# M906X.net
KiCad netlist of a schematic drawn in EAGLE
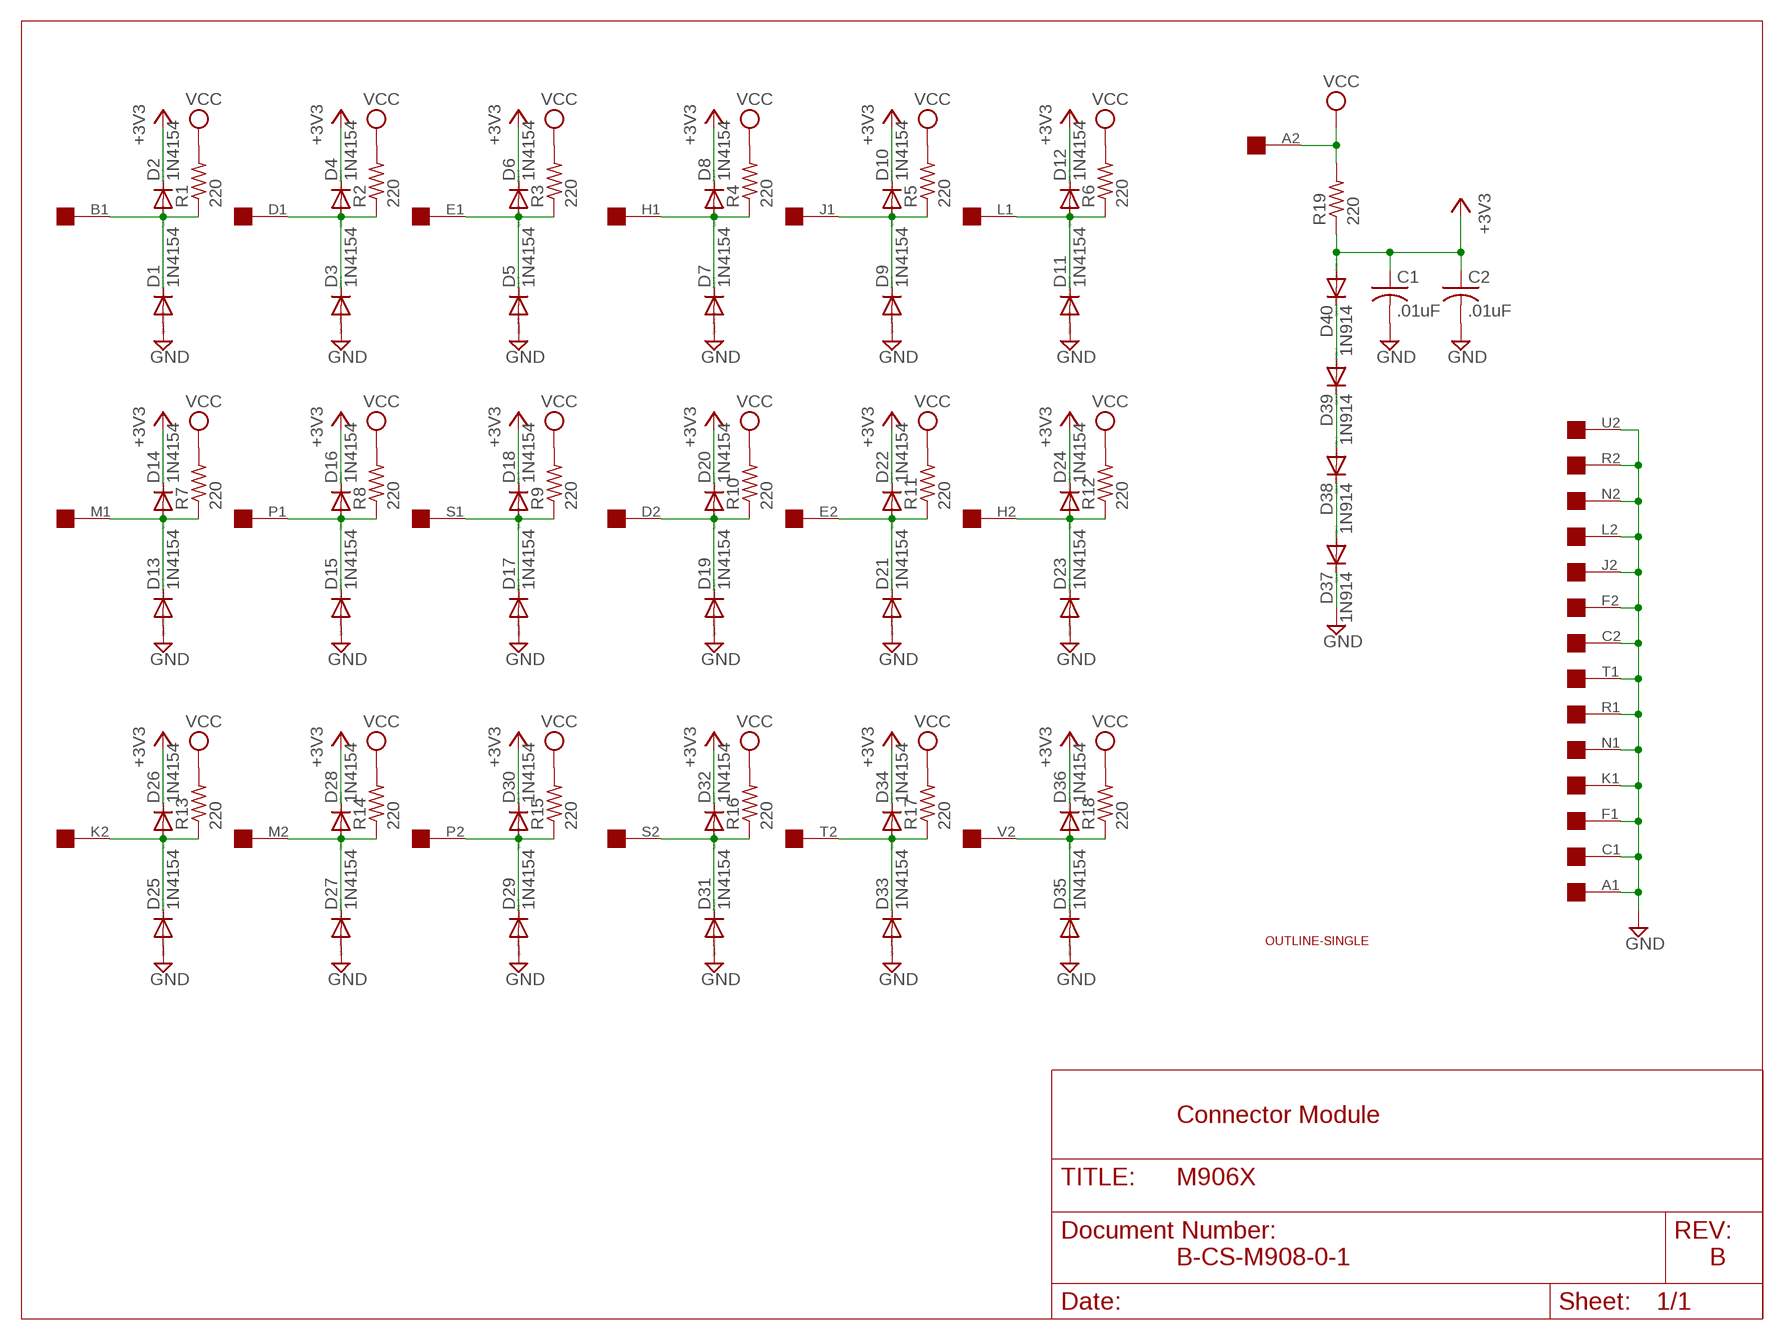
[diagram p0: schematic, sheet 1]

(export (version "E")
  (design (tool "Eeschema 10.0.6"))
  (components
    (comp (ref "C1")
      (value ".01uF")
      (footprint "eagle-import:C050-025X075")
      (libsource (lib "eagle-import") (part "C-US050-025X075"))
    )
    (comp (ref "C2")
      (value ".01uF")
      (footprint "eagle-import:C050-025X075")
      (libsource (lib "eagle-import") (part "C-US050-025X075"))
    )
    (comp (ref "D1")
      (value "1N4154")
      (footprint "eagle-import:DO35-10")
      (libsource (lib "eagle-import") (part "1N4148DO35-10"))
    )
    (comp (ref "D2")
      (value "1N4154")
      (footprint "eagle-import:DO35-10")
      (libsource (lib "eagle-import") (part "1N4148DO35-10"))
    )
    (comp (ref "D3")
      (value "1N4154")
      (footprint "eagle-import:DO35-10")
      (libsource (lib "eagle-import") (part "1N4148DO35-10"))
    )
    (comp (ref "D4")
      (value "1N4154")
      (footprint "eagle-import:DO35-10")
      (libsource (lib "eagle-import") (part "1N4148DO35-10"))
    )
    (comp (ref "D5")
      (value "1N4154")
      (footprint "eagle-import:DO35-10")
      (libsource (lib "eagle-import") (part "1N4148DO35-10"))
    )
    (comp (ref "D6")
      (value "1N4154")
      (footprint "eagle-import:DO35-10")
      (libsource (lib "eagle-import") (part "1N4148DO35-10"))
    )
    (comp (ref "D7")
      (value "1N4154")
      (footprint "eagle-import:DO35-10")
      (libsource (lib "eagle-import") (part "1N4148DO35-10"))
    )
    (comp (ref "D8")
      (value "1N4154")
      (footprint "eagle-import:DO35-10")
      (libsource (lib "eagle-import") (part "1N4148DO35-10"))
    )
    (comp (ref "D9")
      (value "1N4154")
      (footprint "eagle-import:DO35-10")
      (libsource (lib "eagle-import") (part "1N4148DO35-10"))
    )
    (comp (ref "D10")
      (value "1N4154")
      (footprint "eagle-import:DO35-10")
      (libsource (lib "eagle-import") (part "1N4148DO35-10"))
    )
    (comp (ref "D11")
      (value "1N4154")
      (footprint "eagle-import:DO35-10")
      (libsource (lib "eagle-import") (part "1N4148DO35-10"))
    )
    (comp (ref "D12")
      (value "1N4154")
      (footprint "eagle-import:DO35-10")
      (libsource (lib "eagle-import") (part "1N4148DO35-10"))
    )
    (comp (ref "D13")
      (value "1N4154")
      (footprint "eagle-import:DO35-10")
      (libsource (lib "eagle-import") (part "1N4148DO35-10"))
    )
    (comp (ref "D14")
      (value "1N4154")
      (footprint "eagle-import:DO35-10")
      (libsource (lib "eagle-import") (part "1N4148DO35-10"))
    )
    (comp (ref "D15")
      (value "1N4154")
      (footprint "eagle-import:DO35-10")
      (libsource (lib "eagle-import") (part "1N4148DO35-10"))
    )
    (comp (ref "D16")
      (value "1N4154")
      (footprint "eagle-import:DO35-10")
      (libsource (lib "eagle-import") (part "1N4148DO35-10"))
    )
    (comp (ref "D17")
      (value "1N4154")
      (footprint "eagle-import:DO35-10")
      (libsource (lib "eagle-import") (part "1N4148DO35-10"))
    )
    (comp (ref "D18")
      (value "1N4154")
      (footprint "eagle-import:DO35-10")
      (libsource (lib "eagle-import") (part "1N4148DO35-10"))
    )
    (comp (ref "D19")
      (value "1N4154")
      (footprint "eagle-import:DO35-10")
      (libsource (lib "eagle-import") (part "1N4148DO35-10"))
    )
    (comp (ref "D20")
      (value "1N4154")
      (footprint "eagle-import:DO35-10")
      (libsource (lib "eagle-import") (part "1N4148DO35-10"))
    )
    (comp (ref "D21")
      (value "1N4154")
      (footprint "eagle-import:DO35-10")
      (libsource (lib "eagle-import") (part "1N4148DO35-10"))
    )
    (comp (ref "D22")
      (value "1N4154")
      (footprint "eagle-import:DO35-10")
      (libsource (lib "eagle-import") (part "1N4148DO35-10"))
    )
    (comp (ref "D23")
      (value "1N4154")
      (footprint "eagle-import:DO35-10")
      (libsource (lib "eagle-import") (part "1N4148DO35-10"))
    )
    (comp (ref "D24")
      (value "1N4154")
      (footprint "eagle-import:DO35-10")
      (libsource (lib "eagle-import") (part "1N4148DO35-10"))
    )
    (comp (ref "D25")
      (value "1N4154")
      (footprint "eagle-import:DO35-10")
      (libsource (lib "eagle-import") (part "1N4148DO35-10"))
    )
    (comp (ref "D26")
      (value "1N4154")
      (footprint "eagle-import:DO35-10")
      (libsource (lib "eagle-import") (part "1N4148DO35-10"))
    )
    (comp (ref "D27")
      (value "1N4154")
      (footprint "eagle-import:DO35-10")
      (libsource (lib "eagle-import") (part "1N4148DO35-10"))
    )
    (comp (ref "D28")
      (value "1N4154")
      (footprint "eagle-import:DO35-10")
      (libsource (lib "eagle-import") (part "1N4148DO35-10"))
    )
    (comp (ref "D29")
      (value "1N4154")
      (footprint "eagle-import:DO35-10")
      (libsource (lib "eagle-import") (part "1N4148DO35-10"))
    )
    (comp (ref "D30")
      (value "1N4154")
      (footprint "eagle-import:DO35-10")
      (libsource (lib "eagle-import") (part "1N4148DO35-10"))
    )
    (comp (ref "D31")
      (value "1N4154")
      (footprint "eagle-import:DO35-10")
      (libsource (lib "eagle-import") (part "1N4148DO35-10"))
    )
    (comp (ref "D32")
      (value "1N4154")
      (footprint "eagle-import:DO35-10")
      (libsource (lib "eagle-import") (part "1N4148DO35-10"))
    )
    (comp (ref "D33")
      (value "1N4154")
      (footprint "eagle-import:DO35-10")
      (libsource (lib "eagle-import") (part "1N4148DO35-10"))
    )
    (comp (ref "D34")
      (value "1N4154")
      (footprint "eagle-import:DO35-10")
      (libsource (lib "eagle-import") (part "1N4148DO35-10"))
    )
    (comp (ref "D35")
      (value "1N4154")
      (footprint "eagle-import:DO35-10")
      (libsource (lib "eagle-import") (part "1N4148DO35-10"))
    )
    (comp (ref "D36")
      (value "1N4154")
      (footprint "eagle-import:DO35-10")
      (libsource (lib "eagle-import") (part "1N4148DO35-10"))
    )
    (comp (ref "D37")
      (value "1N914")
      (footprint "eagle-import:DO35-10")
      (libsource (lib "eagle-import") (part "1N4148DO35-10"))
    )
    (comp (ref "D38")
      (value "1N914")
      (footprint "eagle-import:DO35-10")
      (libsource (lib "eagle-import") (part "1N4148DO35-10"))
    )
    (comp (ref "D39")
      (value "1N914")
      (footprint "eagle-import:DO35-10")
      (libsource (lib "eagle-import") (part "1N4148DO35-10"))
    )
    (comp (ref "D40")
      (value "1N914")
      (footprint "eagle-import:DO35-10")
      (libsource (lib "eagle-import") (part "1N4148DO35-10"))
    )
    (comp (ref "R1")
      (value "220")
      (footprint "eagle-import:0207_10")
      (libsource (lib "eagle-import") (part "R-US_0207/10"))
    )
    (comp (ref "R2")
      (value "220")
      (footprint "eagle-import:0207_10")
      (libsource (lib "eagle-import") (part "R-US_0207/10"))
    )
    (comp (ref "R3")
      (value "220")
      (footprint "eagle-import:0207_10")
      (libsource (lib "eagle-import") (part "R-US_0207/10"))
    )
    (comp (ref "R4")
      (value "220")
      (footprint "eagle-import:0207_10")
      (libsource (lib "eagle-import") (part "R-US_0207/10"))
    )
    (comp (ref "R5")
      (value "220")
      (footprint "eagle-import:0207_10")
      (libsource (lib "eagle-import") (part "R-US_0207/10"))
    )
    (comp (ref "R6")
      (value "220")
      (footprint "eagle-import:0207_10")
      (libsource (lib "eagle-import") (part "R-US_0207/10"))
    )
    (comp (ref "R7")
      (value "220")
      (footprint "eagle-import:0207_10")
      (libsource (lib "eagle-import") (part "R-US_0207/10"))
    )
    (comp (ref "R8")
      (value "220")
      (footprint "eagle-import:0207_10")
      (libsource (lib "eagle-import") (part "R-US_0207/10"))
    )
    (comp (ref "R9")
      (value "220")
      (footprint "eagle-import:0207_10")
      (libsource (lib "eagle-import") (part "R-US_0207/10"))
    )
    (comp (ref "R10")
      (value "220")
      (footprint "eagle-import:0207_10")
      (libsource (lib "eagle-import") (part "R-US_0207/10"))
    )
    (comp (ref "R11")
      (value "220")
      (footprint "eagle-import:0207_10")
      (libsource (lib "eagle-import") (part "R-US_0207/10"))
    )
    (comp (ref "R12")
      (value "220")
      (footprint "eagle-import:0207_10")
      (libsource (lib "eagle-import") (part "R-US_0207/10"))
    )
    (comp (ref "R13")
      (value "220")
      (footprint "eagle-import:0207_10")
      (libsource (lib "eagle-import") (part "R-US_0207/10"))
    )
    (comp (ref "R14")
      (value "220")
      (footprint "eagle-import:0207_10")
      (libsource (lib "eagle-import") (part "R-US_0207/10"))
    )
    (comp (ref "R15")
      (value "220")
      (footprint "eagle-import:0207_10")
      (libsource (lib "eagle-import") (part "R-US_0207/10"))
    )
    (comp (ref "R16")
      (value "220")
      (footprint "eagle-import:0207_10")
      (libsource (lib "eagle-import") (part "R-US_0207/10"))
    )
    (comp (ref "R17")
      (value "220")
      (footprint "eagle-import:0207_10")
      (libsource (lib "eagle-import") (part "R-US_0207/10"))
    )
    (comp (ref "R18")
      (value "220")
      (footprint "eagle-import:0207_10")
      (libsource (lib "eagle-import") (part "R-US_0207/10"))
    )
    (comp (ref "R19")
      (value "220")
      (footprint "eagle-import:0207_10")
      (libsource (lib "eagle-import") (part "R-US_0207/10"))
    )
    (comp (ref "U$1")
      (value "SINGLE")
      (footprint "eagle-import:EDGE-CON2")
      (libsource (lib "eagle-import") (part "SINGLE"))
    )
    (comp (ref "U$2")
      (value "OUTLINE-SINGLE")
      (footprint "eagle-import:SINGLE")
      (libsource (lib "eagle-import") (part "OUTLINE-SINGLE"))
    )
  )
  (nets
    (net (code "1") (name "+3V3") (class "Default")
      (node (ref "C1") (pin "1") (pinfunction "1_1") (pintype "passive"))
      (node (ref "C2") (pin "1") (pinfunction "1_1") (pintype "passive"))
      (node (ref "D10") (pin "C") (pinfunction "C_C") (pintype "passive"))
      (node (ref "D12") (pin "C") (pinfunction "C_C") (pintype "passive"))
      (node (ref "D14") (pin "C") (pinfunction "C_C") (pintype "passive"))
      (node (ref "D16") (pin "C") (pinfunction "C_C") (pintype "passive"))
      (node (ref "D18") (pin "C") (pinfunction "C_C") (pintype "passive"))
      (node (ref "D2") (pin "C") (pinfunction "C_C") (pintype "passive"))
      (node (ref "D20") (pin "C") (pinfunction "C_C") (pintype "passive"))
      (node (ref "D22") (pin "C") (pinfunction "C_C") (pintype "passive"))
      (node (ref "D24") (pin "C") (pinfunction "C_C") (pintype "passive"))
      (node (ref "D26") (pin "C") (pinfunction "C_C") (pintype "passive"))
      (node (ref "D28") (pin "C") (pinfunction "C_C") (pintype "passive"))
      (node (ref "D30") (pin "C") (pinfunction "C_C") (pintype "passive"))
      (node (ref "D32") (pin "C") (pinfunction "C_C") (pintype "passive"))
      (node (ref "D34") (pin "C") (pinfunction "C_C") (pintype "passive"))
      (node (ref "D36") (pin "C") (pinfunction "C_C") (pintype "passive"))
      (node (ref "D4") (pin "C") (pinfunction "C_C") (pintype "passive"))
      (node (ref "D40") (pin "A") (pinfunction "A_A") (pintype "passive"))
      (node (ref "D6") (pin "C") (pinfunction "C_C") (pintype "passive"))
      (node (ref "D8") (pin "C") (pinfunction "C_C") (pintype "passive"))
      (node (ref "R19") (pin "1") (pinfunction "1_1") (pintype "passive"))
    )
    (net (code "2") (name "GND") (class "Default")
      (node (ref "C1") (pin "2") (pinfunction "2_2") (pintype "passive"))
      (node (ref "C2") (pin "2") (pinfunction "2_2") (pintype "passive"))
      (node (ref "D1") (pin "A") (pinfunction "A_A") (pintype "passive"))
      (node (ref "D11") (pin "A") (pinfunction "A_A") (pintype "passive"))
      (node (ref "D13") (pin "A") (pinfunction "A_A") (pintype "passive"))
      (node (ref "D15") (pin "A") (pinfunction "A_A") (pintype "passive"))
      (node (ref "D17") (pin "A") (pinfunction "A_A") (pintype "passive"))
      (node (ref "D19") (pin "A") (pinfunction "A_A") (pintype "passive"))
      (node (ref "D21") (pin "A") (pinfunction "A_A") (pintype "passive"))
      (node (ref "D23") (pin "A") (pinfunction "A_A") (pintype "passive"))
      (node (ref "D25") (pin "A") (pinfunction "A_A") (pintype "passive"))
      (node (ref "D27") (pin "A") (pinfunction "A_A") (pintype "passive"))
      (node (ref "D29") (pin "A") (pinfunction "A_A") (pintype "passive"))
      (node (ref "D3") (pin "A") (pinfunction "A_A") (pintype "passive"))
      (node (ref "D31") (pin "A") (pinfunction "A_A") (pintype "passive"))
      (node (ref "D33") (pin "A") (pinfunction "A_A") (pintype "passive"))
      (node (ref "D35") (pin "A") (pinfunction "A_A") (pintype "passive"))
      (node (ref "D37") (pin "C") (pinfunction "C_C") (pintype "passive"))
      (node (ref "D5") (pin "A") (pinfunction "A_A") (pintype "passive"))
      (node (ref "D7") (pin "A") (pinfunction "A_A") (pintype "passive"))
      (node (ref "D9") (pin "A") (pinfunction "A_A") (pintype "passive"))
      (node (ref "U$1") (pin "A1") (pinfunction "1_A1") (pintype "bidirectional"))
      (node (ref "U$1") (pin "C1") (pinfunction "1_C1") (pintype "bidirectional"))
      (node (ref "U$1") (pin "C2") (pinfunction "1_C2") (pintype "bidirectional"))
      (node (ref "U$1") (pin "F1") (pinfunction "1_F1") (pintype "bidirectional"))
      (node (ref "U$1") (pin "F2") (pinfunction "1_F2") (pintype "bidirectional"))
      (node (ref "U$1") (pin "J2") (pinfunction "1_J2") (pintype "bidirectional"))
      (node (ref "U$1") (pin "K1") (pinfunction "1_K1") (pintype "bidirectional"))
      (node (ref "U$1") (pin "L2") (pinfunction "1_L2") (pintype "bidirectional"))
      (node (ref "U$1") (pin "N1") (pinfunction "1_N1") (pintype "bidirectional"))
      (node (ref "U$1") (pin "N2") (pinfunction "1_N2") (pintype "bidirectional"))
      (node (ref "U$1") (pin "R1") (pinfunction "1_R1") (pintype "bidirectional"))
      (node (ref "U$1") (pin "R2") (pinfunction "1_R2") (pintype "bidirectional"))
      (node (ref "U$1") (pin "T1") (pinfunction "1_T1") (pintype "bidirectional"))
      (node (ref "U$1") (pin "U2") (pinfunction "1_U2") (pintype "bidirectional"))
    )
    (net (code "3") (name "Net-(D37-PadA)") (class "Default")
      (node (ref "D37") (pin "A") (pinfunction "A_A") (pintype "passive"))
      (node (ref "D38") (pin "C") (pinfunction "C_C") (pintype "passive"))
    )
    (net (code "4") (name "Net-(D38-PadA)") (class "Default")
      (node (ref "D38") (pin "A") (pinfunction "A_A") (pintype "passive"))
      (node (ref "D39") (pin "C") (pinfunction "C_C") (pintype "passive"))
    )
    (net (code "5") (name "Net-(D39-PadA)") (class "Default")
      (node (ref "D39") (pin "A") (pinfunction "A_A") (pintype "passive"))
      (node (ref "D40") (pin "C") (pinfunction "C_C") (pintype "passive"))
    )
    (net (code "6") (name "Net-(U$1AC-1)") (class "Default")
      (node (ref "D17") (pin "C") (pinfunction "C_C") (pintype "passive"))
      (node (ref "D18") (pin "A") (pinfunction "A_A") (pintype "passive"))
      (node (ref "R9") (pin "1") (pinfunction "1_1") (pintype "passive"))
      (node (ref "U$1") (pin "S1") (pinfunction "1_S1") (pintype "bidirectional"))
    )
    (net (code "7") (name "Net-(U$1AD-1)") (class "Default")
      (node (ref "D31") (pin "C") (pinfunction "C_C") (pintype "passive"))
      (node (ref "D32") (pin "A") (pinfunction "A_A") (pintype "passive"))
      (node (ref "R16") (pin "1") (pinfunction "1_1") (pintype "passive"))
      (node (ref "U$1") (pin "S2") (pinfunction "1_S2") (pintype "bidirectional"))
    )
    (net (code "8") (name "Net-(U$1AF-1)") (class "Default")
      (node (ref "D33") (pin "C") (pinfunction "C_C") (pintype "passive"))
      (node (ref "D34") (pin "A") (pinfunction "A_A") (pintype "passive"))
      (node (ref "R17") (pin "1") (pinfunction "1_1") (pintype "passive"))
      (node (ref "U$1") (pin "T2") (pinfunction "1_T2") (pintype "bidirectional"))
    )
    (net (code "9") (name "Net-(U$1AJ-1)") (class "Default")
      (node (ref "D35") (pin "C") (pinfunction "C_C") (pintype "passive"))
      (node (ref "D36") (pin "A") (pinfunction "A_A") (pintype "passive"))
      (node (ref "R18") (pin "1") (pinfunction "1_1") (pintype "passive"))
      (node (ref "U$1") (pin "V2") (pinfunction "1_V2") (pintype "bidirectional"))
    )
    (net (code "10") (name "Net-(U$1C-1)") (class "Default")
      (node (ref "D1") (pin "C") (pinfunction "C_C") (pintype "passive"))
      (node (ref "D2") (pin "A") (pinfunction "A_A") (pintype "passive"))
      (node (ref "R1") (pin "1") (pinfunction "1_1") (pintype "passive"))
      (node (ref "U$1") (pin "B1") (pinfunction "1_B1") (pintype "bidirectional"))
    )
    (net (code "11") (name "Net-(U$1G-1)") (class "Default")
      (node (ref "D3") (pin "C") (pinfunction "C_C") (pintype "passive"))
      (node (ref "D4") (pin "A") (pinfunction "A_A") (pintype "passive"))
      (node (ref "R2") (pin "1") (pinfunction "1_1") (pintype "passive"))
      (node (ref "U$1") (pin "D1") (pinfunction "1_D1") (pintype "bidirectional"))
    )
    (net (code "12") (name "Net-(U$1H-1)") (class "Default")
      (node (ref "D19") (pin "C") (pinfunction "C_C") (pintype "passive"))
      (node (ref "D20") (pin "A") (pinfunction "A_A") (pintype "passive"))
      (node (ref "R10") (pin "1") (pinfunction "1_1") (pintype "passive"))
      (node (ref "U$1") (pin "D2") (pinfunction "1_D2") (pintype "bidirectional"))
    )
    (net (code "13") (name "Net-(U$1I-1)") (class "Default")
      (node (ref "D5") (pin "C") (pinfunction "C_C") (pintype "passive"))
      (node (ref "D6") (pin "A") (pinfunction "A_A") (pintype "passive"))
      (node (ref "R3") (pin "1") (pinfunction "1_1") (pintype "passive"))
      (node (ref "U$1") (pin "E1") (pinfunction "1_E1") (pintype "bidirectional"))
    )
    (net (code "14") (name "Net-(U$1J-1)") (class "Default")
      (node (ref "D21") (pin "C") (pinfunction "C_C") (pintype "passive"))
      (node (ref "D22") (pin "A") (pinfunction "A_A") (pintype "passive"))
      (node (ref "R11") (pin "1") (pinfunction "1_1") (pintype "passive"))
      (node (ref "U$1") (pin "E2") (pinfunction "1_E2") (pintype "bidirectional"))
    )
    (net (code "15") (name "Net-(U$1M-1)") (class "Default")
      (node (ref "D7") (pin "C") (pinfunction "C_C") (pintype "passive"))
      (node (ref "D8") (pin "A") (pinfunction "A_A") (pintype "passive"))
      (node (ref "R4") (pin "1") (pinfunction "1_1") (pintype "passive"))
      (node (ref "U$1") (pin "H1") (pinfunction "1_H1") (pintype "bidirectional"))
    )
    (net (code "16") (name "Net-(U$1N-1)") (class "Default")
      (node (ref "D23") (pin "C") (pinfunction "C_C") (pintype "passive"))
      (node (ref "D24") (pin "A") (pinfunction "A_A") (pintype "passive"))
      (node (ref "R12") (pin "1") (pinfunction "1_1") (pintype "passive"))
      (node (ref "U$1") (pin "H2") (pinfunction "1_H2") (pintype "bidirectional"))
    )
    (net (code "17") (name "Net-(U$1O-1)") (class "Default")
      (node (ref "D10") (pin "A") (pinfunction "A_A") (pintype "passive"))
      (node (ref "D9") (pin "C") (pinfunction "C_C") (pintype "passive"))
      (node (ref "R5") (pin "1") (pinfunction "1_1") (pintype "passive"))
      (node (ref "U$1") (pin "J1") (pinfunction "1_J1") (pintype "bidirectional"))
    )
    (net (code "18") (name "Net-(U$1R-1)") (class "Default")
      (node (ref "D25") (pin "C") (pinfunction "C_C") (pintype "passive"))
      (node (ref "D26") (pin "A") (pinfunction "A_A") (pintype "passive"))
      (node (ref "R13") (pin "1") (pinfunction "1_1") (pintype "passive"))
      (node (ref "U$1") (pin "K2") (pinfunction "1_K2") (pintype "bidirectional"))
    )
    (net (code "19") (name "Net-(U$1S-1)") (class "Default")
      (node (ref "D11") (pin "C") (pinfunction "C_C") (pintype "passive"))
      (node (ref "D12") (pin "A") (pinfunction "A_A") (pintype "passive"))
      (node (ref "R6") (pin "1") (pinfunction "1_1") (pintype "passive"))
      (node (ref "U$1") (pin "L1") (pinfunction "1_L1") (pintype "bidirectional"))
    )
    (net (code "20") (name "Net-(U$1U-1)") (class "Default")
      (node (ref "D13") (pin "C") (pinfunction "C_C") (pintype "passive"))
      (node (ref "D14") (pin "A") (pinfunction "A_A") (pintype "passive"))
      (node (ref "R7") (pin "1") (pinfunction "1_1") (pintype "passive"))
      (node (ref "U$1") (pin "M1") (pinfunction "1_M1") (pintype "bidirectional"))
    )
    (net (code "21") (name "Net-(U$1V-1)") (class "Default")
      (node (ref "D27") (pin "C") (pinfunction "C_C") (pintype "passive"))
      (node (ref "D28") (pin "A") (pinfunction "A_A") (pintype "passive"))
      (node (ref "R14") (pin "1") (pinfunction "1_1") (pintype "passive"))
      (node (ref "U$1") (pin "M2") (pinfunction "1_M2") (pintype "bidirectional"))
    )
    (net (code "22") (name "Net-(U$1Y-1)") (class "Default")
      (node (ref "D15") (pin "C") (pinfunction "C_C") (pintype "passive"))
      (node (ref "D16") (pin "A") (pinfunction "A_A") (pintype "passive"))
      (node (ref "R8") (pin "1") (pinfunction "1_1") (pintype "passive"))
      (node (ref "U$1") (pin "P1") (pinfunction "1_P1") (pintype "bidirectional"))
    )
    (net (code "23") (name "Net-(U$1Z-1)") (class "Default")
      (node (ref "D29") (pin "C") (pinfunction "C_C") (pintype "passive"))
      (node (ref "D30") (pin "A") (pinfunction "A_A") (pintype "passive"))
      (node (ref "R15") (pin "1") (pinfunction "1_1") (pintype "passive"))
      (node (ref "U$1") (pin "P2") (pinfunction "1_P2") (pintype "bidirectional"))
    )
    (net (code "24") (name "VCC") (class "Default")
      (node (ref "R1") (pin "2") (pinfunction "2_2") (pintype "passive"))
      (node (ref "R10") (pin "2") (pinfunction "2_2") (pintype "passive"))
      (node (ref "R11") (pin "2") (pinfunction "2_2") (pintype "passive"))
      (node (ref "R12") (pin "2") (pinfunction "2_2") (pintype "passive"))
      (node (ref "R13") (pin "2") (pinfunction "2_2") (pintype "passive"))
      (node (ref "R14") (pin "2") (pinfunction "2_2") (pintype "passive"))
      (node (ref "R15") (pin "2") (pinfunction "2_2") (pintype "passive"))
      (node (ref "R16") (pin "2") (pinfunction "2_2") (pintype "passive"))
      (node (ref "R17") (pin "2") (pinfunction "2_2") (pintype "passive"))
      (node (ref "R18") (pin "2") (pinfunction "2_2") (pintype "passive"))
      (node (ref "R19") (pin "2") (pinfunction "2_2") (pintype "passive"))
      (node (ref "R2") (pin "2") (pinfunction "2_2") (pintype "passive"))
      (node (ref "R3") (pin "2") (pinfunction "2_2") (pintype "passive"))
      (node (ref "R4") (pin "2") (pinfunction "2_2") (pintype "passive"))
      (node (ref "R5") (pin "2") (pinfunction "2_2") (pintype "passive"))
      (node (ref "R6") (pin "2") (pinfunction "2_2") (pintype "passive"))
      (node (ref "R7") (pin "2") (pinfunction "2_2") (pintype "passive"))
      (node (ref "R8") (pin "2") (pinfunction "2_2") (pintype "passive"))
      (node (ref "R9") (pin "2") (pinfunction "2_2") (pintype "passive"))
      (node (ref "U$1") (pin "A2") (pinfunction "1_A2") (pintype "bidirectional"))
    )
  )
)
